# Bias.net
KiCad netlist of a schematic drawn in Altium Designer
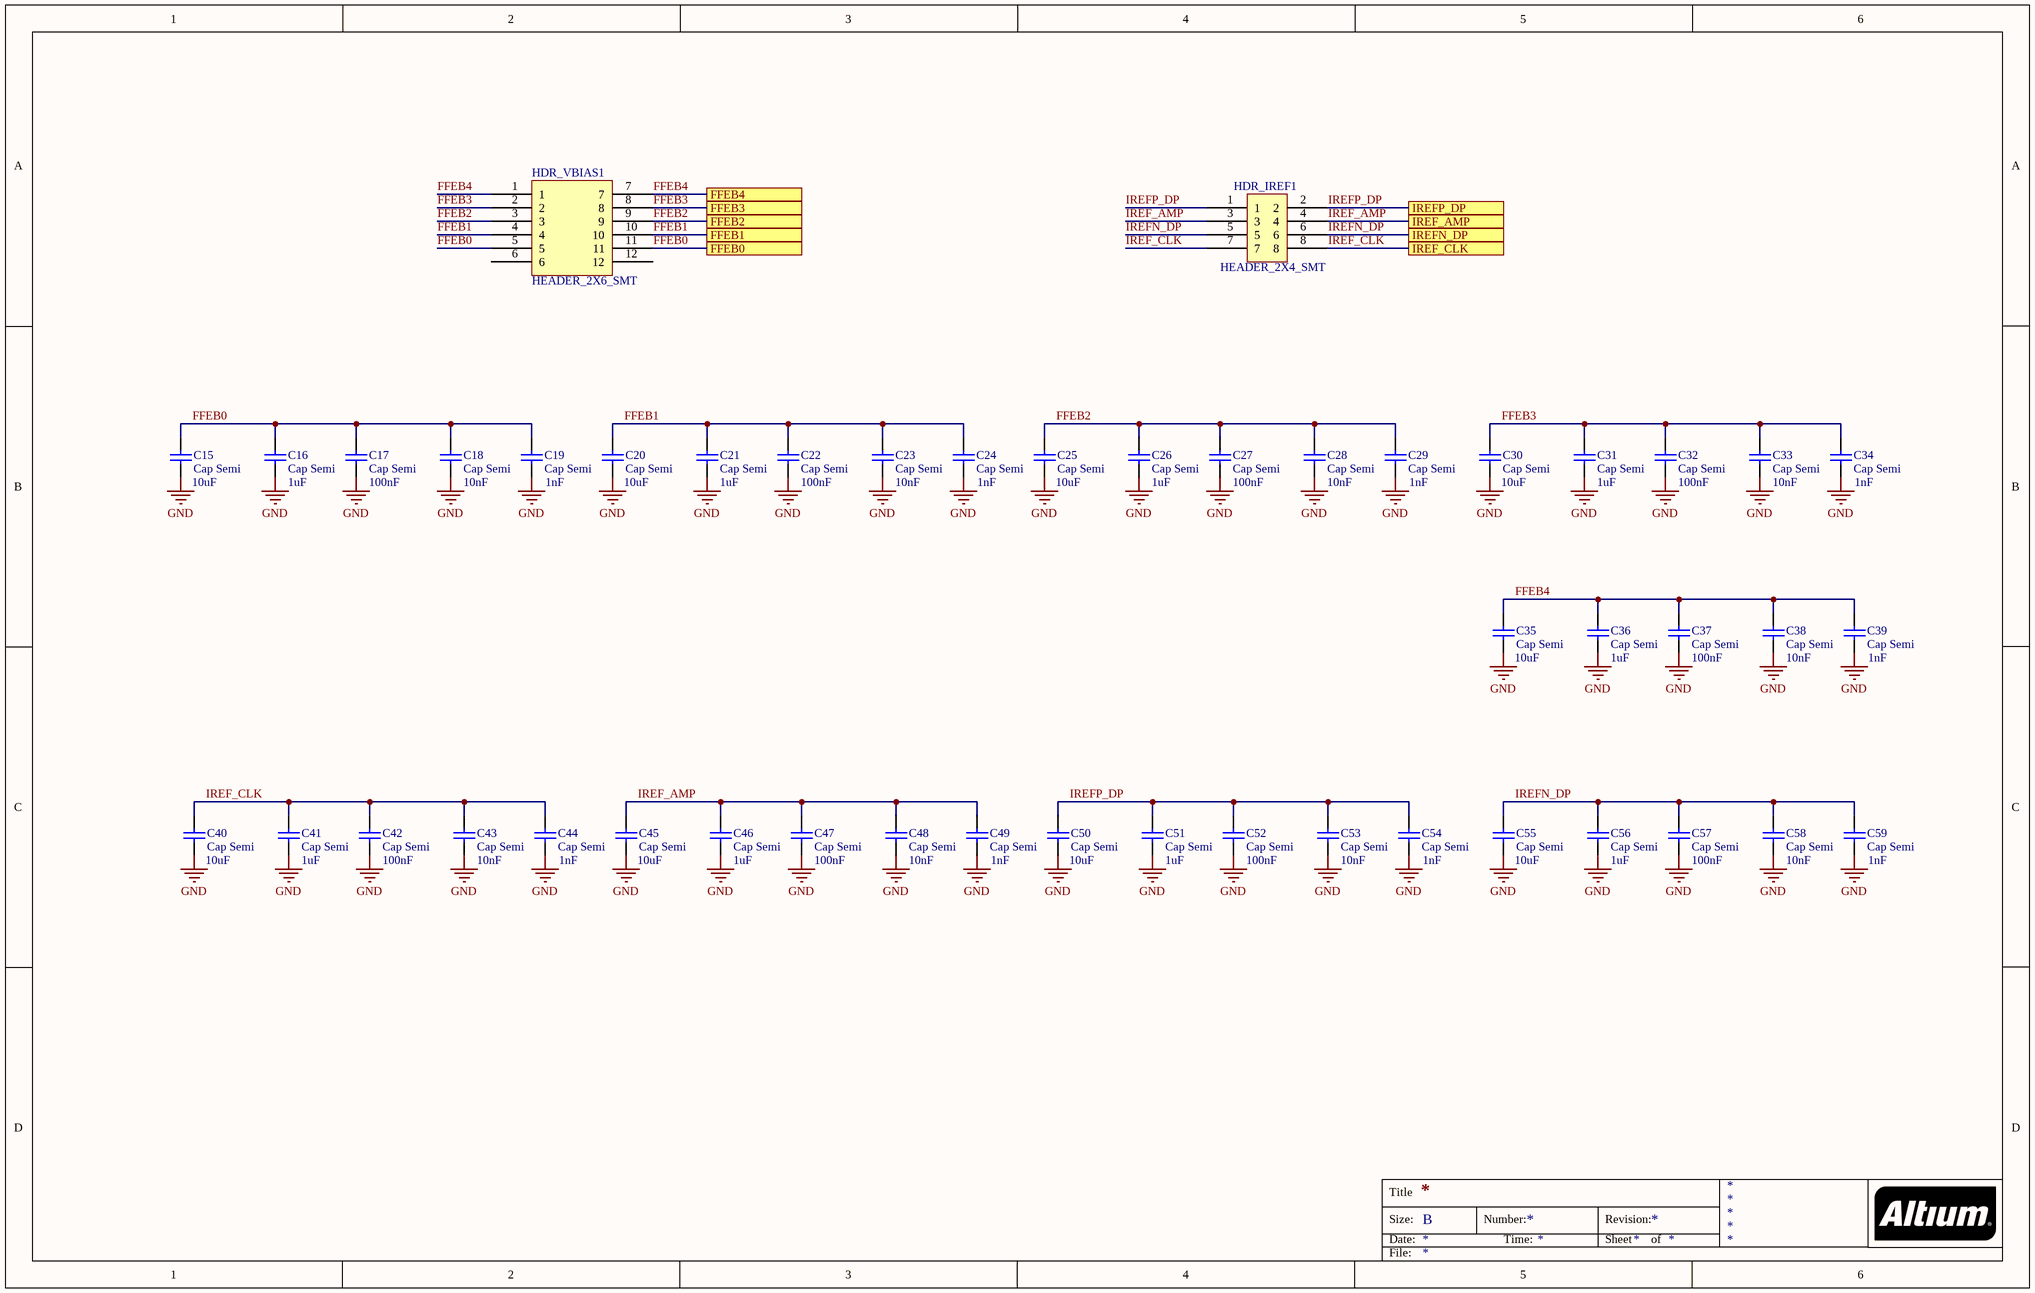
[diagram p0: Bias.SchDoc]

(export (version "E")
  (design (tool "Eeschema 10.0.6"))
  (components
    (comp (ref "C15")
      (value "Cap Semi")
      (footprint "1608[0603]")
      (description "Capacitor (Semiconductor SIM Model)")
      (fields (field (name "ALTIUM_VALUE") "10uF") (field (name "PUBLISHER") "Altium Limited"))
      (libsource (lib "Miscellaneous Devices") (part "Cap Semi"))
    )
    (comp (ref "C16")
      (value "Cap Semi")
      (footprint "1608[0603]")
      (description "Capacitor (Semiconductor SIM Model)")
      (fields (field (name "ALTIUM_VALUE") "1uF") (field (name "PUBLISHER") "Altium Limited"))
      (libsource (lib "Miscellaneous Devices") (part "Cap Semi"))
    )
    (comp (ref "C17")
      (value "Cap Semi")
      (footprint "1608[0603]")
      (description "Capacitor (Semiconductor SIM Model)")
      (fields (field (name "ALTIUM_VALUE") "100nF") (field (name "PUBLISHER") "Altium Limited"))
      (libsource (lib "Miscellaneous Devices") (part "Cap Semi"))
    )
    (comp (ref "C18")
      (value "Cap Semi")
      (footprint "1608[0603]")
      (description "Capacitor (Semiconductor SIM Model)")
      (fields (field (name "ALTIUM_VALUE") "10nF") (field (name "PUBLISHER") "Altium Limited"))
      (libsource (lib "Miscellaneous Devices") (part "Cap Semi"))
    )
    (comp (ref "C19")
      (value "Cap Semi")
      (footprint "1608[0603]")
      (description "Capacitor (Semiconductor SIM Model)")
      (fields (field (name "ALTIUM_VALUE") "1nF") (field (name "PUBLISHER") "Altium Limited"))
      (libsource (lib "Miscellaneous Devices") (part "Cap Semi"))
    )
    (comp (ref "C20")
      (value "Cap Semi")
      (footprint "1608[0603]")
      (description "Capacitor (Semiconductor SIM Model)")
      (fields (field (name "ALTIUM_VALUE") "10uF") (field (name "PUBLISHER") "Altium Limited"))
      (libsource (lib "Miscellaneous Devices") (part "Cap Semi"))
    )
    (comp (ref "C21")
      (value "Cap Semi")
      (footprint "1608[0603]")
      (description "Capacitor (Semiconductor SIM Model)")
      (fields (field (name "ALTIUM_VALUE") "1uF") (field (name "PUBLISHER") "Altium Limited"))
      (libsource (lib "Miscellaneous Devices") (part "Cap Semi"))
    )
    (comp (ref "C22")
      (value "Cap Semi")
      (footprint "1608[0603]")
      (description "Capacitor (Semiconductor SIM Model)")
      (fields (field (name "ALTIUM_VALUE") "100nF") (field (name "PUBLISHER") "Altium Limited"))
      (libsource (lib "Miscellaneous Devices") (part "Cap Semi"))
    )
    (comp (ref "C23")
      (value "Cap Semi")
      (footprint "1608[0603]")
      (description "Capacitor (Semiconductor SIM Model)")
      (fields (field (name "ALTIUM_VALUE") "10nF") (field (name "PUBLISHER") "Altium Limited"))
      (libsource (lib "Miscellaneous Devices") (part "Cap Semi"))
    )
    (comp (ref "C24")
      (value "Cap Semi")
      (footprint "1608[0603]")
      (description "Capacitor (Semiconductor SIM Model)")
      (fields (field (name "ALTIUM_VALUE") "1nF") (field (name "PUBLISHER") "Altium Limited"))
      (libsource (lib "Miscellaneous Devices") (part "Cap Semi"))
    )
    (comp (ref "C25")
      (value "Cap Semi")
      (footprint "1608[0603]")
      (description "Capacitor (Semiconductor SIM Model)")
      (fields (field (name "ALTIUM_VALUE") "10uF") (field (name "PUBLISHER") "Altium Limited"))
      (libsource (lib "Miscellaneous Devices") (part "Cap Semi"))
    )
    (comp (ref "C26")
      (value "Cap Semi")
      (footprint "1608[0603]")
      (description "Capacitor (Semiconductor SIM Model)")
      (fields (field (name "ALTIUM_VALUE") "1uF") (field (name "PUBLISHER") "Altium Limited"))
      (libsource (lib "Miscellaneous Devices") (part "Cap Semi"))
    )
    (comp (ref "C27")
      (value "Cap Semi")
      (footprint "1608[0603]")
      (description "Capacitor (Semiconductor SIM Model)")
      (fields (field (name "ALTIUM_VALUE") "100nF") (field (name "PUBLISHER") "Altium Limited"))
      (libsource (lib "Miscellaneous Devices") (part "Cap Semi"))
    )
    (comp (ref "C28")
      (value "Cap Semi")
      (footprint "1608[0603]")
      (description "Capacitor (Semiconductor SIM Model)")
      (fields (field (name "ALTIUM_VALUE") "10nF") (field (name "PUBLISHER") "Altium Limited"))
      (libsource (lib "Miscellaneous Devices") (part "Cap Semi"))
    )
    (comp (ref "C29")
      (value "Cap Semi")
      (footprint "1608[0603]")
      (description "Capacitor (Semiconductor SIM Model)")
      (fields (field (name "ALTIUM_VALUE") "1nF") (field (name "PUBLISHER") "Altium Limited"))
      (libsource (lib "Miscellaneous Devices") (part "Cap Semi"))
    )
    (comp (ref "C30")
      (value "Cap Semi")
      (footprint "1608[0603]")
      (description "Capacitor (Semiconductor SIM Model)")
      (fields (field (name "ALTIUM_VALUE") "10uF") (field (name "PUBLISHER") "Altium Limited"))
      (libsource (lib "Miscellaneous Devices") (part "Cap Semi"))
    )
    (comp (ref "C31")
      (value "Cap Semi")
      (footprint "1608[0603]")
      (description "Capacitor (Semiconductor SIM Model)")
      (fields (field (name "ALTIUM_VALUE") "1uF") (field (name "PUBLISHER") "Altium Limited"))
      (libsource (lib "Miscellaneous Devices") (part "Cap Semi"))
    )
    (comp (ref "C32")
      (value "Cap Semi")
      (footprint "1608[0603]")
      (description "Capacitor (Semiconductor SIM Model)")
      (fields (field (name "ALTIUM_VALUE") "100nF") (field (name "PUBLISHER") "Altium Limited"))
      (libsource (lib "Miscellaneous Devices") (part "Cap Semi"))
    )
    (comp (ref "C33")
      (value "Cap Semi")
      (footprint "1608[0603]")
      (description "Capacitor (Semiconductor SIM Model)")
      (fields (field (name "ALTIUM_VALUE") "10nF") (field (name "PUBLISHER") "Altium Limited"))
      (libsource (lib "Miscellaneous Devices") (part "Cap Semi"))
    )
    (comp (ref "C34")
      (value "Cap Semi")
      (footprint "1608[0603]")
      (description "Capacitor (Semiconductor SIM Model)")
      (fields (field (name "ALTIUM_VALUE") "1nF") (field (name "PUBLISHER") "Altium Limited"))
      (libsource (lib "Miscellaneous Devices") (part "Cap Semi"))
    )
    (comp (ref "C35")
      (value "Cap Semi")
      (footprint "1608[0603]")
      (description "Capacitor (Semiconductor SIM Model)")
      (fields (field (name "ALTIUM_VALUE") "10uF") (field (name "PUBLISHER") "Altium Limited"))
      (libsource (lib "Miscellaneous Devices") (part "Cap Semi"))
    )
    (comp (ref "C36")
      (value "Cap Semi")
      (footprint "1608[0603]")
      (description "Capacitor (Semiconductor SIM Model)")
      (fields (field (name "ALTIUM_VALUE") "1uF") (field (name "PUBLISHER") "Altium Limited"))
      (libsource (lib "Miscellaneous Devices") (part "Cap Semi"))
    )
    (comp (ref "C37")
      (value "Cap Semi")
      (footprint "1608[0603]")
      (description "Capacitor (Semiconductor SIM Model)")
      (fields (field (name "ALTIUM_VALUE") "100nF") (field (name "PUBLISHER") "Altium Limited"))
      (libsource (lib "Miscellaneous Devices") (part "Cap Semi"))
    )
    (comp (ref "C38")
      (value "Cap Semi")
      (footprint "1608[0603]")
      (description "Capacitor (Semiconductor SIM Model)")
      (fields (field (name "ALTIUM_VALUE") "10nF") (field (name "PUBLISHER") "Altium Limited"))
      (libsource (lib "Miscellaneous Devices") (part "Cap Semi"))
    )
    (comp (ref "C39")
      (value "Cap Semi")
      (footprint "1608[0603]")
      (description "Capacitor (Semiconductor SIM Model)")
      (fields (field (name "ALTIUM_VALUE") "1nF") (field (name "PUBLISHER") "Altium Limited"))
      (libsource (lib "Miscellaneous Devices") (part "Cap Semi"))
    )
    (comp (ref "C40")
      (value "Cap Semi")
      (footprint "1608[0603]")
      (description "Capacitor (Semiconductor SIM Model)")
      (fields (field (name "ALTIUM_VALUE") "10uF") (field (name "PUBLISHER") "Altium Limited"))
      (libsource (lib "Miscellaneous Devices") (part "Cap Semi"))
    )
    (comp (ref "C41")
      (value "Cap Semi")
      (footprint "1608[0603]")
      (description "Capacitor (Semiconductor SIM Model)")
      (fields (field (name "ALTIUM_VALUE") "1uF") (field (name "PUBLISHER") "Altium Limited"))
      (libsource (lib "Miscellaneous Devices") (part "Cap Semi"))
    )
    (comp (ref "C42")
      (value "Cap Semi")
      (footprint "1608[0603]")
      (description "Capacitor (Semiconductor SIM Model)")
      (fields (field (name "ALTIUM_VALUE") "100nF") (field (name "PUBLISHER") "Altium Limited"))
      (libsource (lib "Miscellaneous Devices") (part "Cap Semi"))
    )
    (comp (ref "C43")
      (value "Cap Semi")
      (footprint "1608[0603]")
      (description "Capacitor (Semiconductor SIM Model)")
      (fields (field (name "ALTIUM_VALUE") "10nF") (field (name "PUBLISHER") "Altium Limited"))
      (libsource (lib "Miscellaneous Devices") (part "Cap Semi"))
    )
    (comp (ref "C44")
      (value "Cap Semi")
      (footprint "1608[0603]")
      (description "Capacitor (Semiconductor SIM Model)")
      (fields (field (name "ALTIUM_VALUE") "1nF") (field (name "PUBLISHER") "Altium Limited"))
      (libsource (lib "Miscellaneous Devices") (part "Cap Semi"))
    )
    (comp (ref "C45")
      (value "Cap Semi")
      (footprint "1608[0603]")
      (description "Capacitor (Semiconductor SIM Model)")
      (fields (field (name "ALTIUM_VALUE") "10uF") (field (name "PUBLISHER") "Altium Limited"))
      (libsource (lib "Miscellaneous Devices") (part "Cap Semi"))
    )
    (comp (ref "C46")
      (value "Cap Semi")
      (footprint "1608[0603]")
      (description "Capacitor (Semiconductor SIM Model)")
      (fields (field (name "ALTIUM_VALUE") "1uF") (field (name "PUBLISHER") "Altium Limited"))
      (libsource (lib "Miscellaneous Devices") (part "Cap Semi"))
    )
    (comp (ref "C47")
      (value "Cap Semi")
      (footprint "1608[0603]")
      (description "Capacitor (Semiconductor SIM Model)")
      (fields (field (name "ALTIUM_VALUE") "100nF") (field (name "PUBLISHER") "Altium Limited"))
      (libsource (lib "Miscellaneous Devices") (part "Cap Semi"))
    )
    (comp (ref "C48")
      (value "Cap Semi")
      (footprint "1608[0603]")
      (description "Capacitor (Semiconductor SIM Model)")
      (fields (field (name "ALTIUM_VALUE") "10nF") (field (name "PUBLISHER") "Altium Limited"))
      (libsource (lib "Miscellaneous Devices") (part "Cap Semi"))
    )
    (comp (ref "C49")
      (value "Cap Semi")
      (footprint "1608[0603]")
      (description "Capacitor (Semiconductor SIM Model)")
      (fields (field (name "ALTIUM_VALUE") "1nF") (field (name "PUBLISHER") "Altium Limited"))
      (libsource (lib "Miscellaneous Devices") (part "Cap Semi"))
    )
    (comp (ref "C50")
      (value "Cap Semi")
      (footprint "1608[0603]")
      (description "Capacitor (Semiconductor SIM Model)")
      (fields (field (name "ALTIUM_VALUE") "10uF") (field (name "PUBLISHER") "Altium Limited"))
      (libsource (lib "Miscellaneous Devices") (part "Cap Semi"))
    )
    (comp (ref "C51")
      (value "Cap Semi")
      (footprint "1608[0603]")
      (description "Capacitor (Semiconductor SIM Model)")
      (fields (field (name "ALTIUM_VALUE") "1uF") (field (name "PUBLISHER") "Altium Limited"))
      (libsource (lib "Miscellaneous Devices") (part "Cap Semi"))
    )
    (comp (ref "C52")
      (value "Cap Semi")
      (footprint "1608[0603]")
      (description "Capacitor (Semiconductor SIM Model)")
      (fields (field (name "ALTIUM_VALUE") "100nF") (field (name "PUBLISHER") "Altium Limited"))
      (libsource (lib "Miscellaneous Devices") (part "Cap Semi"))
    )
    (comp (ref "C53")
      (value "Cap Semi")
      (footprint "1608[0603]")
      (description "Capacitor (Semiconductor SIM Model)")
      (fields (field (name "ALTIUM_VALUE") "10nF") (field (name "PUBLISHER") "Altium Limited"))
      (libsource (lib "Miscellaneous Devices") (part "Cap Semi"))
    )
    (comp (ref "C54")
      (value "Cap Semi")
      (footprint "1608[0603]")
      (description "Capacitor (Semiconductor SIM Model)")
      (fields (field (name "ALTIUM_VALUE") "1nF") (field (name "PUBLISHER") "Altium Limited"))
      (libsource (lib "Miscellaneous Devices") (part "Cap Semi"))
    )
    (comp (ref "C55")
      (value "Cap Semi")
      (footprint "1608[0603]")
      (description "Capacitor (Semiconductor SIM Model)")
      (fields (field (name "ALTIUM_VALUE") "10uF") (field (name "PUBLISHER") "Altium Limited"))
      (libsource (lib "Miscellaneous Devices") (part "Cap Semi"))
    )
    (comp (ref "C56")
      (value "Cap Semi")
      (footprint "1608[0603]")
      (description "Capacitor (Semiconductor SIM Model)")
      (fields (field (name "ALTIUM_VALUE") "1uF") (field (name "PUBLISHER") "Altium Limited"))
      (libsource (lib "Miscellaneous Devices") (part "Cap Semi"))
    )
    (comp (ref "C57")
      (value "Cap Semi")
      (footprint "1608[0603]")
      (description "Capacitor (Semiconductor SIM Model)")
      (fields (field (name "ALTIUM_VALUE") "100nF") (field (name "PUBLISHER") "Altium Limited"))
      (libsource (lib "Miscellaneous Devices") (part "Cap Semi"))
    )
    (comp (ref "C58")
      (value "Cap Semi")
      (footprint "1608[0603]")
      (description "Capacitor (Semiconductor SIM Model)")
      (fields (field (name "ALTIUM_VALUE") "10nF") (field (name "PUBLISHER") "Altium Limited"))
      (libsource (lib "Miscellaneous Devices") (part "Cap Semi"))
    )
    (comp (ref "C59")
      (value "Cap Semi")
      (footprint "1608[0603]")
      (description "Capacitor (Semiconductor SIM Model)")
      (fields (field (name "ALTIUM_VALUE") "1nF") (field (name "PUBLISHER") "Altium Limited"))
      (libsource (lib "Miscellaneous Devices") (part "Cap Semi"))
    )
    (comp (ref "HDR_IREF1")
      (value "HEADER_2X4_SMT")
      (footprint "HEADER_2X4_SMT")
      (libsource (lib "200G_TX_LIB") (part "HEADER_2X4_SMT"))
    )
    (comp (ref "HDR_VBIAS1")
      (value "HEADER_2X6_SMT")
      (footprint "HDR2X6_SMT")
      (libsource (lib "200G_TX_LIB") (part "HEADER_2X6_SMT"))
    )
  )
  (nets
    (net (code "1") (name "/FFEB0") (class "Default")
      (node (ref "C15") (pin "2") (pinfunction "2_2") (pintype "passive"))
      (node (ref "C16") (pin "2") (pinfunction "2_2") (pintype "passive"))
      (node (ref "C17") (pin "2") (pinfunction "2_2") (pintype "passive"))
      (node (ref "C18") (pin "2") (pinfunction "2_2") (pintype "passive"))
      (node (ref "C19") (pin "2") (pinfunction "2_2") (pintype "passive"))
      (node (ref "HDR_VBIAS1") (pin "11") (pinfunction "11_11") (pintype "passive"))
      (node (ref "HDR_VBIAS1") (pin "5") (pinfunction "5_5") (pintype "passive"))
    )
    (net (code "2") (name "/FFEB1") (class "Default")
      (node (ref "C20") (pin "2") (pinfunction "2_2") (pintype "passive"))
      (node (ref "C21") (pin "2") (pinfunction "2_2") (pintype "passive"))
      (node (ref "C22") (pin "2") (pinfunction "2_2") (pintype "passive"))
      (node (ref "C23") (pin "2") (pinfunction "2_2") (pintype "passive"))
      (node (ref "C24") (pin "2") (pinfunction "2_2") (pintype "passive"))
      (node (ref "HDR_VBIAS1") (pin "10") (pinfunction "10_10") (pintype "passive"))
      (node (ref "HDR_VBIAS1") (pin "4") (pinfunction "4_4") (pintype "passive"))
    )
    (net (code "3") (name "/FFEB2") (class "Default")
      (node (ref "C25") (pin "2") (pinfunction "2_2") (pintype "passive"))
      (node (ref "C26") (pin "2") (pinfunction "2_2") (pintype "passive"))
      (node (ref "C27") (pin "2") (pinfunction "2_2") (pintype "passive"))
      (node (ref "C28") (pin "2") (pinfunction "2_2") (pintype "passive"))
      (node (ref "C29") (pin "2") (pinfunction "2_2") (pintype "passive"))
      (node (ref "HDR_VBIAS1") (pin "3") (pinfunction "3_3") (pintype "passive"))
      (node (ref "HDR_VBIAS1") (pin "9") (pinfunction "9_9") (pintype "passive"))
    )
    (net (code "4") (name "/FFEB3") (class "Default")
      (node (ref "C30") (pin "2") (pinfunction "2_2") (pintype "passive"))
      (node (ref "C31") (pin "2") (pinfunction "2_2") (pintype "passive"))
      (node (ref "C32") (pin "2") (pinfunction "2_2") (pintype "passive"))
      (node (ref "C33") (pin "2") (pinfunction "2_2") (pintype "passive"))
      (node (ref "C34") (pin "2") (pinfunction "2_2") (pintype "passive"))
      (node (ref "HDR_VBIAS1") (pin "2") (pinfunction "2_2") (pintype "passive"))
      (node (ref "HDR_VBIAS1") (pin "8") (pinfunction "8_8") (pintype "passive"))
    )
    (net (code "5") (name "/FFEB4") (class "Default")
      (node (ref "C35") (pin "2") (pinfunction "2_2") (pintype "passive"))
      (node (ref "C36") (pin "2") (pinfunction "2_2") (pintype "passive"))
      (node (ref "C37") (pin "2") (pinfunction "2_2") (pintype "passive"))
      (node (ref "C38") (pin "2") (pinfunction "2_2") (pintype "passive"))
      (node (ref "C39") (pin "2") (pinfunction "2_2") (pintype "passive"))
      (node (ref "HDR_VBIAS1") (pin "1") (pinfunction "1_1") (pintype "passive"))
      (node (ref "HDR_VBIAS1") (pin "7") (pinfunction "7_7") (pintype "passive"))
    )
    (net (code "6") (name "/IREFN_DP") (class "Default")
      (node (ref "C55") (pin "2") (pinfunction "2_2") (pintype "passive"))
      (node (ref "C56") (pin "2") (pinfunction "2_2") (pintype "passive"))
      (node (ref "C57") (pin "2") (pinfunction "2_2") (pintype "passive"))
      (node (ref "C58") (pin "2") (pinfunction "2_2") (pintype "passive"))
      (node (ref "C59") (pin "2") (pinfunction "2_2") (pintype "passive"))
      (node (ref "HDR_IREF1") (pin "5") (pinfunction "5_5") (pintype "passive"))
      (node (ref "HDR_IREF1") (pin "6") (pinfunction "6_6") (pintype "passive"))
    )
    (net (code "7") (name "/IREFP_DP") (class "Default")
      (node (ref "C50") (pin "2") (pinfunction "2_2") (pintype "passive"))
      (node (ref "C51") (pin "2") (pinfunction "2_2") (pintype "passive"))
      (node (ref "C52") (pin "2") (pinfunction "2_2") (pintype "passive"))
      (node (ref "C53") (pin "2") (pinfunction "2_2") (pintype "passive"))
      (node (ref "C54") (pin "2") (pinfunction "2_2") (pintype "passive"))
      (node (ref "HDR_IREF1") (pin "1") (pinfunction "1_1") (pintype "passive"))
      (node (ref "HDR_IREF1") (pin "2") (pinfunction "2_2") (pintype "passive"))
    )
    (net (code "8") (name "/IREF_AMP") (class "Default")
      (node (ref "C45") (pin "2") (pinfunction "2_2") (pintype "passive"))
      (node (ref "C46") (pin "2") (pinfunction "2_2") (pintype "passive"))
      (node (ref "C47") (pin "2") (pinfunction "2_2") (pintype "passive"))
      (node (ref "C48") (pin "2") (pinfunction "2_2") (pintype "passive"))
      (node (ref "C49") (pin "2") (pinfunction "2_2") (pintype "passive"))
      (node (ref "HDR_IREF1") (pin "3") (pinfunction "3_3") (pintype "passive"))
      (node (ref "HDR_IREF1") (pin "4") (pinfunction "4_4") (pintype "passive"))
    )
    (net (code "9") (name "/IREF_CLK") (class "Default")
      (node (ref "C40") (pin "2") (pinfunction "2_2") (pintype "passive"))
      (node (ref "C41") (pin "2") (pinfunction "2_2") (pintype "passive"))
      (node (ref "C42") (pin "2") (pinfunction "2_2") (pintype "passive"))
      (node (ref "C43") (pin "2") (pinfunction "2_2") (pintype "passive"))
      (node (ref "C44") (pin "2") (pinfunction "2_2") (pintype "passive"))
      (node (ref "HDR_IREF1") (pin "7") (pinfunction "7_7") (pintype "passive"))
      (node (ref "HDR_IREF1") (pin "8") (pinfunction "8_8") (pintype "passive"))
    )
    (net (code "10") (name "GND") (class "Default")
      (node (ref "C15") (pin "1") (pinfunction "1_1") (pintype "passive"))
      (node (ref "C16") (pin "1") (pinfunction "1_1") (pintype "passive"))
      (node (ref "C17") (pin "1") (pinfunction "1_1") (pintype "passive"))
      (node (ref "C18") (pin "1") (pinfunction "1_1") (pintype "passive"))
      (node (ref "C19") (pin "1") (pinfunction "1_1") (pintype "passive"))
      (node (ref "C20") (pin "1") (pinfunction "1_1") (pintype "passive"))
      (node (ref "C21") (pin "1") (pinfunction "1_1") (pintype "passive"))
      (node (ref "C22") (pin "1") (pinfunction "1_1") (pintype "passive"))
      (node (ref "C23") (pin "1") (pinfunction "1_1") (pintype "passive"))
      (node (ref "C24") (pin "1") (pinfunction "1_1") (pintype "passive"))
      (node (ref "C25") (pin "1") (pinfunction "1_1") (pintype "passive"))
      (node (ref "C26") (pin "1") (pinfunction "1_1") (pintype "passive"))
      (node (ref "C27") (pin "1") (pinfunction "1_1") (pintype "passive"))
      (node (ref "C28") (pin "1") (pinfunction "1_1") (pintype "passive"))
      (node (ref "C29") (pin "1") (pinfunction "1_1") (pintype "passive"))
      (node (ref "C30") (pin "1") (pinfunction "1_1") (pintype "passive"))
      (node (ref "C31") (pin "1") (pinfunction "1_1") (pintype "passive"))
      (node (ref "C32") (pin "1") (pinfunction "1_1") (pintype "passive"))
      (node (ref "C33") (pin "1") (pinfunction "1_1") (pintype "passive"))
      (node (ref "C34") (pin "1") (pinfunction "1_1") (pintype "passive"))
      (node (ref "C35") (pin "1") (pinfunction "1_1") (pintype "passive"))
      (node (ref "C36") (pin "1") (pinfunction "1_1") (pintype "passive"))
      (node (ref "C37") (pin "1") (pinfunction "1_1") (pintype "passive"))
      (node (ref "C38") (pin "1") (pinfunction "1_1") (pintype "passive"))
      (node (ref "C39") (pin "1") (pinfunction "1_1") (pintype "passive"))
      (node (ref "C40") (pin "1") (pinfunction "1_1") (pintype "passive"))
      (node (ref "C41") (pin "1") (pinfunction "1_1") (pintype "passive"))
      (node (ref "C42") (pin "1") (pinfunction "1_1") (pintype "passive"))
      (node (ref "C43") (pin "1") (pinfunction "1_1") (pintype "passive"))
      (node (ref "C44") (pin "1") (pinfunction "1_1") (pintype "passive"))
      (node (ref "C45") (pin "1") (pinfunction "1_1") (pintype "passive"))
      (node (ref "C46") (pin "1") (pinfunction "1_1") (pintype "passive"))
      (node (ref "C47") (pin "1") (pinfunction "1_1") (pintype "passive"))
      (node (ref "C48") (pin "1") (pinfunction "1_1") (pintype "passive"))
      (node (ref "C49") (pin "1") (pinfunction "1_1") (pintype "passive"))
      (node (ref "C50") (pin "1") (pinfunction "1_1") (pintype "passive"))
      (node (ref "C51") (pin "1") (pinfunction "1_1") (pintype "passive"))
      (node (ref "C52") (pin "1") (pinfunction "1_1") (pintype "passive"))
      (node (ref "C53") (pin "1") (pinfunction "1_1") (pintype "passive"))
      (node (ref "C54") (pin "1") (pinfunction "1_1") (pintype "passive"))
      (node (ref "C55") (pin "1") (pinfunction "1_1") (pintype "passive"))
      (node (ref "C56") (pin "1") (pinfunction "1_1") (pintype "passive"))
      (node (ref "C57") (pin "1") (pinfunction "1_1") (pintype "passive"))
      (node (ref "C58") (pin "1") (pinfunction "1_1") (pintype "passive"))
      (node (ref "C59") (pin "1") (pinfunction "1_1") (pintype "passive"))
    )
    (net (code "11") (name "unconnected-(HDR_VBIAS1-Pad6)") (class "Default")
      (node (ref "HDR_VBIAS1") (pin "6") (pinfunction "6_6") (pintype "passive"))
    )
    (net (code "12") (name "unconnected-(HDR_VBIAS1-Pad12)") (class "Default")
      (node (ref "HDR_VBIAS1") (pin "12") (pinfunction "12_12") (pintype "passive"))
    )
  )
)
